# Rauchmelder_2_1b.net
KiCad netlist of a schematic drawn in EAGLE
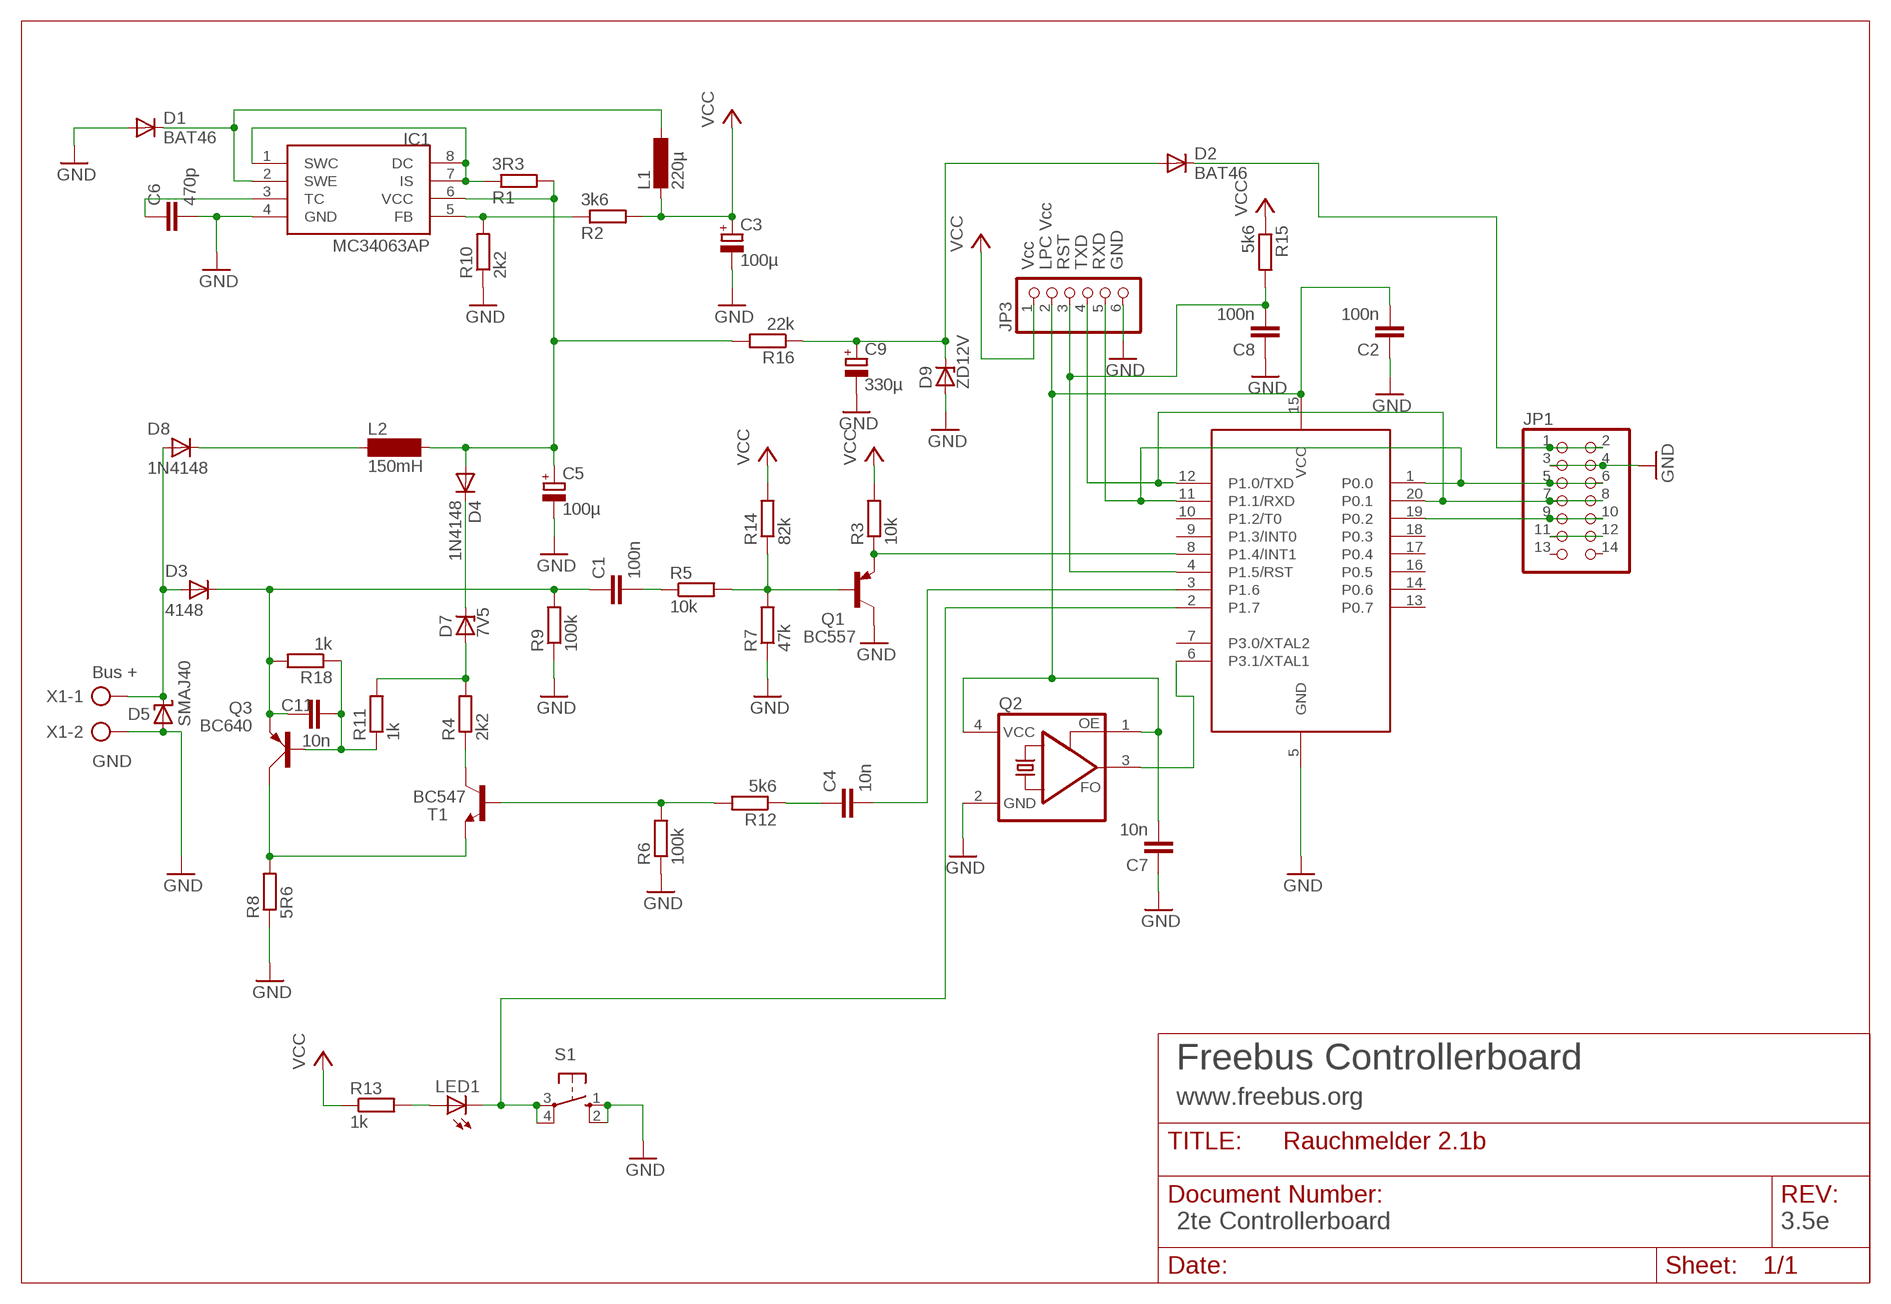
[diagram p0: schematic, sheet 1]

(export (version "E")
  (design (tool "Eeschema 10.0.6"))
  (components
    (comp (ref "89LPC922")
      (value "89LPC922")
      (footprint "eagle-import:DIL20")
      (libsource (lib "eagle-import") (part "89LPC922"))
    )
    (comp (ref "C1")
      (value "100n")
      (footprint "eagle-import:C025-024X044")
      (libsource (lib "eagle-import") (part "C-EU025-024X044"))
    )
    (comp (ref "C2")
      (value "100n")
      (footprint "eagle-import:C025-024X044")
      (libsource (lib "eagle-import") (part "C-EU025-024X044"))
    )
    (comp (ref "C3")
      (value "100µ")
      (footprint "eagle-import:E2,5-6")
      (libsource (lib "eagle-import") (part "CPOL-EUE2.5-6"))
    )
    (comp (ref "C4")
      (value "10n")
      (footprint "eagle-import:C025-024X044")
      (libsource (lib "eagle-import") (part "C-EU025-024X044"))
    )
    (comp (ref "C5")
      (value "100µ")
      (footprint "eagle-import:E3,5-8")
      (libsource (lib "eagle-import") (part "CPOL-EUE3.5-8"))
    )
    (comp (ref "C6")
      (value "470p")
      (footprint "eagle-import:C025-024X044")
      (libsource (lib "eagle-import") (part "C-EU025-024X044"))
    )
    (comp (ref "C7")
      (value "10n")
      (footprint "eagle-import:C1206")
      (libsource (lib "eagle-import") (part "C-EUC1206"))
    )
    (comp (ref "C8")
      (value "100n")
      (footprint "eagle-import:C025-024X044")
      (libsource (lib "eagle-import") (part "C-EU025-024X044"))
    )
    (comp (ref "C9")
      (value "330µ")
      (footprint "eagle-import:E3,5-8")
      (libsource (lib "eagle-import") (part "CPOL-EUE3.5-8"))
    )
    (comp (ref "C11")
      (value "10n")
      (footprint "eagle-import:C025-024X044")
      (libsource (lib "eagle-import") (part "C-EU025-024X044"))
    )
    (comp (ref "D1")
      (value "BAT46")
      (footprint "eagle-import:DO34-7")
      (libsource (lib "eagle-import") (part "BAT81"))
    )
    (comp (ref "D2")
      (value "BAT46")
      (footprint "eagle-import:DO34-7")
      (libsource (lib "eagle-import") (part "BAT81"))
    )
    (comp (ref "D3")
      (value "4148")
      (footprint "eagle-import:DO35-S")
      (libsource (lib "eagle-import") (part "DO35-STEHEND"))
    )
    (comp (ref "D4")
      (value "1N4148")
      (footprint "eagle-import:DO35-10")
      (libsource (lib "eagle-import") (part "1N4148"))
    )
    (comp (ref "D5")
      (value "SMAJ40")
      (footprint "eagle-import:SMBJ")
      (libsource (lib "eagle-import") (part "SUPPRESSOR-SMBJ"))
    )
    (comp (ref "D7")
      (value "7V5")
      (footprint "eagle-import:ZDIO-2.5")
      (libsource (lib "eagle-import") (part "BZX85ZDIOV"))
    )
    (comp (ref "D8")
      (value "1N4148")
      (footprint "eagle-import:DO35-S")
      (libsource (lib "eagle-import") (part "DO35-STEHEND"))
    )
    (comp (ref "D9")
      (value "ZD12V")
      (footprint "eagle-import:DO34Z7")
      (libsource (lib "eagle-import") (part "BZX90"))
    )
    (comp (ref "IC1")
      (value "MC34063AP")
      (footprint "eagle-import:DIL08")
      (libsource (lib "eagle-import") (part "MC34063AP"))
    )
    (comp (ref "JP1")
      (value "PINHD-2X7")
      (footprint "eagle-import:2X07")
      (libsource (lib "eagle-import") (part "PINHD-2X7"))
    )
    (comp (ref "JP3")
      (value "PINHD-1X6")
      (footprint "eagle-import:1X06")
      (libsource (lib "eagle-import") (part "PINHD-1X6"))
    )
    (comp (ref "L1")
      (value "220µ")
      (footprint "eagle-import:0207_12")
      (libsource (lib "eagle-import") (part "L-EU0207/12"))
    )
    (comp (ref "L2")
      (value "150mH")
      (footprint "eagle-import:BS11")
      (libsource (lib "eagle-import") (part "BS11"))
    )
    (comp (ref "LED1")
      (value "LED3MM")
      (footprint "eagle-import:LED3MM")
      (libsource (lib "eagle-import") (part "LED3MM"))
    )
    (comp (ref "Q1")
      (value "BC557")
      (footprint "eagle-import:TO92")
      (libsource (lib "eagle-import") (part "BC557"))
    )
    (comp (ref "Q2")
      (value "ASFL")
      (footprint "eagle-import:ASF")
      (libsource (lib "eagle-import") (part "ASFL"))
    )
    (comp (ref "Q3")
      (value "BC640")
      (footprint "eagle-import:SOT54D")
      (libsource (lib "eagle-import") (part "BC640"))
    )
    (comp (ref "R1")
      (value "3R3")
      (footprint "eagle-import:0207_7")
      (libsource (lib "eagle-import") (part "R-EU_0207/7"))
    )
    (comp (ref "R2")
      (value "3k6")
      (footprint "eagle-import:0207_7")
      (libsource (lib "eagle-import") (part "R-EU_0207/7"))
    )
    (comp (ref "R3")
      (value "10k")
      (footprint "eagle-import:0207_7")
      (libsource (lib "eagle-import") (part "R-EU_0207/7"))
    )
    (comp (ref "R4")
      (value "2k2")
      (footprint "eagle-import:0207_2V")
      (libsource (lib "eagle-import") (part "R-EU_0207/2V"))
    )
    (comp (ref "R5")
      (value "10k")
      (footprint "eagle-import:0207_7")
      (libsource (lib "eagle-import") (part "R-EU_0207/7"))
    )
    (comp (ref "R6")
      (value "100k")
      (footprint "eagle-import:0207_2V")
      (libsource (lib "eagle-import") (part "R-EU_0207/2V"))
    )
    (comp (ref "R7")
      (value "47k")
      (footprint "eagle-import:0207_7")
      (libsource (lib "eagle-import") (part "R-EU_0207/7"))
    )
    (comp (ref "R8")
      (value "5R6")
      (footprint "eagle-import:0207_2V")
      (libsource (lib "eagle-import") (part "R-EU_0207/2V"))
    )
    (comp (ref "R9")
      (value "100k")
      (footprint "eagle-import:0207_7")
      (libsource (lib "eagle-import") (part "R-EU_0207/7"))
    )
    (comp (ref "R10")
      (value "2k2")
      (footprint "eagle-import:0207_7")
      (libsource (lib "eagle-import") (part "R-EU_0207/7"))
    )
    (comp (ref "R11")
      (value "1k")
      (footprint "eagle-import:0207_2V")
      (libsource (lib "eagle-import") (part "R-EU_0207/2V"))
    )
    (comp (ref "R12")
      (value "5k6")
      (footprint "eagle-import:0207_7")
      (libsource (lib "eagle-import") (part "R-EU_0207/7"))
    )
    (comp (ref "R13")
      (value "1k")
      (footprint "eagle-import:0207_7")
      (libsource (lib "eagle-import") (part "R-EU_0207/7"))
    )
    (comp (ref "R14")
      (value "82k")
      (footprint "eagle-import:0207_7")
      (libsource (lib "eagle-import") (part "R-EU_0207/7"))
    )
    (comp (ref "R15")
      (value "5k6")
      (footprint "eagle-import:0207_2V")
      (libsource (lib "eagle-import") (part "R-EU_0207/2V"))
    )
    (comp (ref "R16")
      (value "22k")
      (footprint "eagle-import:0207_2V")
      (libsource (lib "eagle-import") (part "R-EU_0207/2V"))
    )
    (comp (ref "R18")
      (value "1k")
      (footprint "eagle-import:0207_2V")
      (libsource (lib "eagle-import") (part "R-EU_0207/2V"))
    )
    (comp (ref "S1")
      (value "10-XX")
      (footprint "eagle-import:B3F-10XX")
      (libsource (lib "eagle-import") (part "10-XX"))
    )
    (comp (ref "T1")
      (value "BC547")
      (footprint "eagle-import:TO92")
      (libsource (lib "eagle-import") (part "BC547"))
    )
    (comp (ref "X1")
      (value "AK500/2")
      (footprint "eagle-import:AK500_2")
      (libsource (lib "eagle-import") (part "AK500/2"))
    )
  )
  (nets
    (net (code "1") (name "GND") (class "Default")
      (node (ref "89LPC922") (pin "5") (pinfunction "GND_5") (pintype "bidirectional"))
      (node (ref "C2") (pin "1") (pinfunction "1_1") (pintype "passive"))
      (node (ref "C3") (pin "-") (pinfunction "-_-") (pintype "passive"))
      (node (ref "C5") (pin "-") (pinfunction "-_-") (pintype "passive"))
      (node (ref "C6") (pin "2") (pinfunction "2_2") (pintype "passive"))
      (node (ref "C7") (pin "1") (pinfunction "1_1") (pintype "passive"))
      (node (ref "C8") (pin "1") (pinfunction "1_1") (pintype "passive"))
      (node (ref "C9") (pin "-") (pinfunction "-_-") (pintype "passive"))
      (node (ref "D1") (pin "A") (pinfunction "A_A") (pintype "passive"))
      (node (ref "D5") (pin "A") (pinfunction "A_A") (pintype "passive"))
      (node (ref "D9") (pin "A") (pinfunction "A_A") (pintype "passive"))
      (node (ref "IC1") (pin "4") (pinfunction "GND_4") (pintype "passive"))
      (node (ref "JP1") (pin "3") (pinfunction "3_3") (pintype "passive"))
      (node (ref "JP1") (pin "4") (pinfunction "4_4") (pintype "passive"))
      (node (ref "JP3") (pin "6") (pinfunction "6_6") (pintype "passive"))
      (node (ref "Q1") (pin "3") (pinfunction "C_3") (pintype "passive"))
      (node (ref "Q2") (pin "2") (pinfunction "GND_2") (pintype "power_in"))
      (node (ref "R10") (pin "1") (pinfunction "1_1") (pintype "passive"))
      (node (ref "R6") (pin "1") (pinfunction "1_1") (pintype "passive"))
      (node (ref "R7") (pin "1") (pinfunction "1_1") (pintype "passive"))
      (node (ref "R8") (pin "1") (pinfunction "1_1") (pintype "passive"))
      (node (ref "R9") (pin "1") (pinfunction "1_1") (pintype "passive"))
      (node (ref "S1") (pin "1") (pinfunction "S_1") (pintype "passive"))
      (node (ref "S1") (pin "2") (pinfunction "S1_2") (pintype "passive"))
      (node (ref "X1") (pin "2") (pinfunction "KL_2") (pintype "passive"))
    )
    (net (code "2") (name "Net-(89LPC922-P0.0)") (class "Default")
      (node (ref "89LPC922") (pin "1") (pinfunction "P0.0_1") (pintype "bidirectional"))
      (node (ref "89LPC922") (pin "11") (pinfunction "P1.1/RXD_11") (pintype "bidirectional"))
      (node (ref "JP1") (pin "5") (pinfunction "5_5") (pintype "passive"))
      (node (ref "JP1") (pin "6") (pinfunction "6_6") (pintype "passive"))
      (node (ref "JP3") (pin "5") (pinfunction "5_5") (pintype "passive"))
    )
    (net (code "3") (name "Net-(89LPC922-P0.1)") (class "Default")
      (node (ref "89LPC922") (pin "12") (pinfunction "P1.0/TXD_12") (pintype "bidirectional"))
      (node (ref "89LPC922") (pin "20") (pinfunction "P0.1_20") (pintype "bidirectional"))
      (node (ref "JP1") (pin "7") (pinfunction "7_7") (pintype "passive"))
      (node (ref "JP1") (pin "8") (pinfunction "8_8") (pintype "passive"))
      (node (ref "JP3") (pin "4") (pinfunction "4_4") (pintype "passive"))
    )
    (net (code "4") (name "Net-(89LPC922-P0.2)") (class "Default")
      (node (ref "89LPC922") (pin "19") (pinfunction "P0.2_19") (pintype "bidirectional"))
      (node (ref "JP1") (pin "10") (pinfunction "10_10") (pintype "passive"))
      (node (ref "JP1") (pin "9") (pinfunction "9_9") (pintype "passive"))
    )
    (net (code "5") (name "Net-(89LPC922-P1.4{slash}INT1)") (class "Default")
      (node (ref "89LPC922") (pin "8") (pinfunction "P1.4/INT1_8") (pintype "bidirectional"))
      (node (ref "Q1") (pin "1") (pinfunction "E_1") (pintype "passive"))
      (node (ref "R3") (pin "1") (pinfunction "1_1") (pintype "passive"))
    )
    (net (code "6") (name "Net-(89LPC922-P1.5{slash}RST)") (class "Default")
      (node (ref "89LPC922") (pin "4") (pinfunction "P1.5/RST_4") (pintype "bidirectional"))
      (node (ref "C8") (pin "2") (pinfunction "2_2") (pintype "passive"))
      (node (ref "JP3") (pin "3") (pinfunction "3_3") (pintype "passive"))
      (node (ref "R15") (pin "2") (pinfunction "2_2") (pintype "passive"))
    )
    (net (code "7") (name "Net-(89LPC922-P1.6)") (class "Default")
      (node (ref "89LPC922") (pin "3") (pinfunction "P1.6_3") (pintype "bidirectional"))
      (node (ref "C4") (pin "2") (pinfunction "2_2") (pintype "passive"))
    )
    (net (code "8") (name "Net-(89LPC922-P1.7)") (class "Default")
      (node (ref "89LPC922") (pin "2") (pinfunction "P1.7_2") (pintype "bidirectional"))
      (node (ref "LED1") (pin "K") (pinfunction "C_K") (pintype "passive"))
      (node (ref "S1") (pin "3") (pinfunction "P_3") (pintype "passive"))
      (node (ref "S1") (pin "4") (pinfunction "P1_4") (pintype "passive"))
    )
    (net (code "9") (name "Net-(89LPC922-P3.1{slash}XTAL1)") (class "Default")
      (node (ref "89LPC922") (pin "6") (pinfunction "P3.1/XTAL1_6") (pintype "bidirectional"))
      (node (ref "Q2") (pin "3") (pinfunction "FO_3") (pintype "output"))
    )
    (net (code "10") (name "Net-(89LPC922-VCC)") (class "Default")
      (node (ref "89LPC922") (pin "15") (pinfunction "VCC_15") (pintype "bidirectional"))
      (node (ref "C2") (pin "2") (pinfunction "2_2") (pintype "passive"))
      (node (ref "C7") (pin "2") (pinfunction "2_2") (pintype "passive"))
      (node (ref "JP3") (pin "2") (pinfunction "2_2") (pintype "passive"))
      (node (ref "Q2") (pin "1") (pinfunction "OE_1") (pintype "input"))
      (node (ref "Q2") (pin "4") (pinfunction "VCC_4") (pintype "power_in"))
    )
    (net (code "11") (name "Net-(C1-Pad2)") (class "Default")
      (node (ref "C1") (pin "2") (pinfunction "2_2") (pintype "passive"))
      (node (ref "R5") (pin "1") (pinfunction "1_1") (pintype "passive"))
    )
    (net (code "12") (name "Net-(C4-Pad1)") (class "Default")
      (node (ref "C4") (pin "1") (pinfunction "1_1") (pintype "passive"))
      (node (ref "R12") (pin "1") (pinfunction "1_1") (pintype "passive"))
    )
    (net (code "13") (name "Net-(C9-Pad+)") (class "Default")
      (node (ref "C9") (pin "+") (pinfunction "+_+") (pintype "passive"))
      (node (ref "D2") (pin "A") (pinfunction "A_A") (pintype "passive"))
      (node (ref "D9") (pin "C") (pinfunction "C_C") (pintype "passive"))
      (node (ref "R16") (pin "1") (pinfunction "1_1") (pintype "passive"))
    )
    (net (code "14") (name "Net-(C11-Pad2)") (class "Default")
      (node (ref "C11") (pin "2") (pinfunction "2_2") (pintype "passive"))
      (node (ref "Q3") (pin "B") (pinfunction "B_B") (pintype "passive"))
      (node (ref "R11") (pin "1") (pinfunction "1_1") (pintype "passive"))
      (node (ref "R18") (pin "1") (pinfunction "1_1") (pintype "passive"))
    )
    (net (code "15") (name "Net-(D2-PadC)") (class "Default")
      (node (ref "D2") (pin "C") (pinfunction "C_C") (pintype "passive"))
      (node (ref "JP1") (pin "1") (pinfunction "1_1") (pintype "passive"))
      (node (ref "JP1") (pin "2") (pinfunction "2_2") (pintype "passive"))
    )
    (net (code "16") (name "Net-(D3-A)") (class "Default")
      (node (ref "D3") (pin "P$1") (pinfunction "A_P$1") (pintype "passive"))
      (node (ref "D5") (pin "C") (pinfunction "C_C") (pintype "passive"))
      (node (ref "D8") (pin "P$1") (pinfunction "A_P$1") (pintype "passive"))
      (node (ref "X1") (pin "1") (pinfunction "KL_1") (pintype "passive"))
    )
    (net (code "17") (name "Net-(D3-B)") (class "Default")
      (node (ref "C1") (pin "1") (pinfunction "1_1") (pintype "passive"))
      (node (ref "C11") (pin "1") (pinfunction "1_1") (pintype "passive"))
      (node (ref "D3") (pin "P$2") (pinfunction "B_P$2") (pintype "passive"))
      (node (ref "Q3") (pin "E") (pinfunction "E_E") (pintype "passive"))
      (node (ref "R18") (pin "2") (pinfunction "2_2") (pintype "passive"))
      (node (ref "R9") (pin "2") (pinfunction "2_2") (pintype "passive"))
    )
    (net (code "18") (name "Net-(D4-PadC)") (class "Default")
      (node (ref "D4") (pin "C") (pinfunction "C_C") (pintype "passive"))
      (node (ref "D7") (pin "C") (pinfunction "C_C") (pintype "passive"))
    )
    (net (code "19") (name "Net-(D7-PadA)") (class "Default")
      (node (ref "D7") (pin "A") (pinfunction "A_A") (pintype "passive"))
      (node (ref "R11") (pin "2") (pinfunction "2_2") (pintype "passive"))
      (node (ref "R4") (pin "2") (pinfunction "2_2") (pintype "passive"))
    )
    (net (code "20") (name "Net-(D8-B)") (class "Default")
      (node (ref "D8") (pin "P$2") (pinfunction "B_P$2") (pintype "passive"))
      (node (ref "L2") (pin "1") (pinfunction "1_1") (pintype "passive"))
    )
    (net (code "21") (name "Net-(IC1-DC)") (class "Default")
      (node (ref "IC1") (pin "1") (pinfunction "SWC_1") (pintype "passive"))
      (node (ref "IC1") (pin "7") (pinfunction "IS_7") (pintype "passive"))
      (node (ref "IC1") (pin "8") (pinfunction "DC_8") (pintype "passive"))
      (node (ref "R1") (pin "1") (pinfunction "1_1") (pintype "passive"))
    )
    (net (code "22") (name "Net-(IC1-FB)") (class "Default")
      (node (ref "IC1") (pin "5") (pinfunction "FB_5") (pintype "passive"))
      (node (ref "R10") (pin "2") (pinfunction "2_2") (pintype "passive"))
      (node (ref "R2") (pin "1") (pinfunction "1_1") (pintype "passive"))
    )
    (net (code "23") (name "Net-(IC1-SWE)") (class "Default")
      (node (ref "D1") (pin "C") (pinfunction "C_C") (pintype "passive"))
      (node (ref "IC1") (pin "2") (pinfunction "SWE_2") (pintype "passive"))
      (node (ref "L1") (pin "1") (pinfunction "1_1") (pintype "passive"))
    )
    (net (code "24") (name "Net-(IC1-TC)") (class "Default")
      (node (ref "C6") (pin "1") (pinfunction "1_1") (pintype "passive"))
      (node (ref "IC1") (pin "3") (pinfunction "TC_3") (pintype "passive"))
    )
    (net (code "25") (name "Net-(IC1-VCC)") (class "Default")
      (node (ref "C5") (pin "+") (pinfunction "+_+") (pintype "passive"))
      (node (ref "D4") (pin "A") (pinfunction "A_A") (pintype "passive"))
      (node (ref "IC1") (pin "6") (pinfunction "VCC_6") (pintype "passive"))
      (node (ref "L2") (pin "2") (pinfunction "2_2") (pintype "passive"))
      (node (ref "R1") (pin "2") (pinfunction "2_2") (pintype "passive"))
      (node (ref "R16") (pin "2") (pinfunction "2_2") (pintype "passive"))
    )
    (net (code "26") (name "Net-(JP1-Pad11)") (class "Default")
      (node (ref "JP1") (pin "11") (pinfunction "11_11") (pintype "passive"))
      (node (ref "JP1") (pin "12") (pinfunction "12_12") (pintype "passive"))
    )
    (net (code "27") (name "Net-(LED1-PadA)") (class "Default")
      (node (ref "LED1") (pin "A") (pinfunction "A_A") (pintype "passive"))
      (node (ref "R13") (pin "2") (pinfunction "2_2") (pintype "passive"))
    )
    (net (code "28") (name "Net-(Q1-B)") (class "Default")
      (node (ref "Q1") (pin "2") (pinfunction "B_2") (pintype "passive"))
      (node (ref "R14") (pin "1") (pinfunction "1_1") (pintype "passive"))
      (node (ref "R5") (pin "2") (pinfunction "2_2") (pintype "passive"))
      (node (ref "R7") (pin "2") (pinfunction "2_2") (pintype "passive"))
    )
    (net (code "29") (name "Net-(T1-B)") (class "Default")
      (node (ref "R12") (pin "2") (pinfunction "2_2") (pintype "passive"))
      (node (ref "R6") (pin "2") (pinfunction "2_2") (pintype "passive"))
      (node (ref "T1") (pin "2") (pinfunction "B_2") (pintype "passive"))
    )
    (net (code "30") (name "Net-(T1-C)") (class "Default")
      (node (ref "R4") (pin "1") (pinfunction "1_1") (pintype "passive"))
      (node (ref "T1") (pin "3") (pinfunction "C_3") (pintype "passive"))
    )
    (net (code "31") (name "Net-(T1-E)") (class "Default")
      (node (ref "Q3") (pin "C") (pinfunction "C_C") (pintype "passive"))
      (node (ref "R8") (pin "2") (pinfunction "2_2") (pintype "passive"))
      (node (ref "T1") (pin "1") (pinfunction "E_1") (pintype "passive"))
    )
    (net (code "32") (name "VCC") (class "Default")
      (node (ref "C3") (pin "+") (pinfunction "+_+") (pintype "passive"))
      (node (ref "JP3") (pin "1") (pinfunction "1_1") (pintype "passive"))
      (node (ref "L1") (pin "2") (pinfunction "2_2") (pintype "passive"))
      (node (ref "R13") (pin "1") (pinfunction "1_1") (pintype "passive"))
      (node (ref "R14") (pin "2") (pinfunction "2_2") (pintype "passive"))
      (node (ref "R15") (pin "1") (pinfunction "1_1") (pintype "passive"))
      (node (ref "R2") (pin "2") (pinfunction "2_2") (pintype "passive"))
      (node (ref "R3") (pin "2") (pinfunction "2_2") (pintype "passive"))
    )
    (net (code "33") (name "unconnected-(89LPC922-P0.3-Pad18)") (class "Default")
      (node (ref "89LPC922") (pin "18") (pinfunction "P0.3_18") (pintype "bidirectional"))
    )
    (net (code "34") (name "unconnected-(89LPC922-P0.4-Pad17)") (class "Default")
      (node (ref "89LPC922") (pin "17") (pinfunction "P0.4_17") (pintype "bidirectional"))
    )
    (net (code "35") (name "unconnected-(89LPC922-P0.5-Pad16)") (class "Default")
      (node (ref "89LPC922") (pin "16") (pinfunction "P0.5_16") (pintype "bidirectional"))
    )
    (net (code "36") (name "unconnected-(89LPC922-P0.6-Pad14)") (class "Default")
      (node (ref "89LPC922") (pin "14") (pinfunction "P0.6_14") (pintype "bidirectional"))
    )
    (net (code "37") (name "unconnected-(89LPC922-P0.7-Pad13)") (class "Default")
      (node (ref "89LPC922") (pin "13") (pinfunction "P0.7_13") (pintype "bidirectional"))
    )
    (net (code "38") (name "unconnected-(89LPC922-P1.2{slash}T0-Pad10)") (class "Default")
      (node (ref "89LPC922") (pin "10") (pinfunction "P1.2/T0_10") (pintype "bidirectional"))
    )
    (net (code "39") (name "unconnected-(89LPC922-P1.3{slash}INT0-Pad9)") (class "Default")
      (node (ref "89LPC922") (pin "9") (pinfunction "P1.3/INT0_9") (pintype "bidirectional"))
    )
    (net (code "40") (name "unconnected-(89LPC922-P3.0{slash}XTAL2-Pad7)") (class "Default")
      (node (ref "89LPC922") (pin "7") (pinfunction "P3.0/XTAL2_7") (pintype "bidirectional"))
    )
    (net (code "41") (name "unconnected-(JP1-Pad13)") (class "Default")
      (node (ref "JP1") (pin "13") (pinfunction "13_13") (pintype "passive"))
    )
    (net (code "42") (name "unconnected-(JP1-Pad14)") (class "Default")
      (node (ref "JP1") (pin "14") (pinfunction "14_14") (pintype "passive"))
    )
  )
)
